# Mega_Shield-criticality.net
KiCad netlist of a schematic drawn in EAGLE
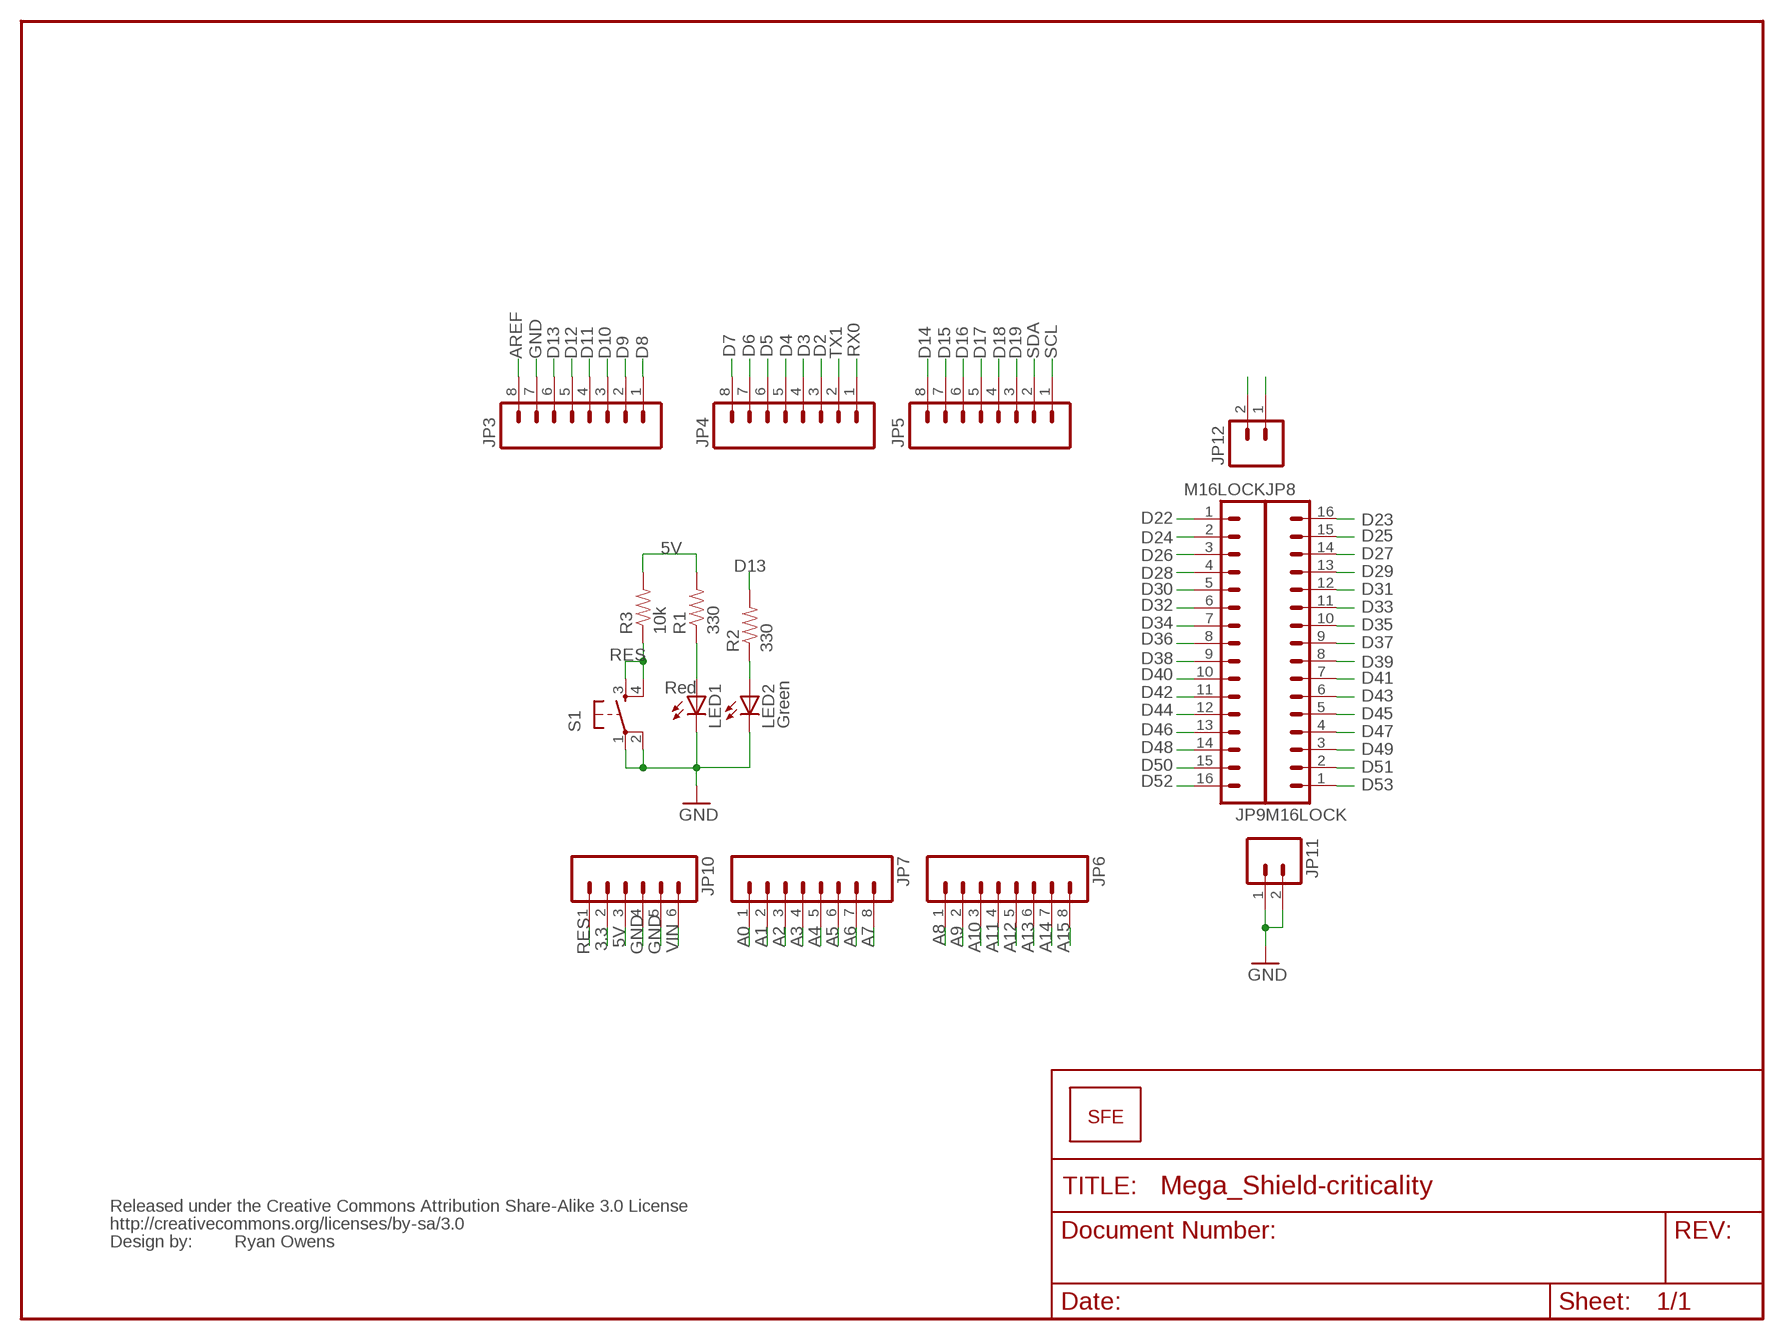
[diagram p0: schematic, sheet 1]

(export (version "E")
  (design (tool "Eeschema 10.0.6"))
  (components
    (comp (ref "JP3")
      (value "M08LOCK")
      (footprint "eagle-import:1X08_LOCK")
      (libsource (lib "eagle-import") (part "M08LOCK"))
    )
    (comp (ref "JP4")
      (value "M08LOCK")
      (footprint "eagle-import:1X08_LOCK")
      (libsource (lib "eagle-import") (part "M08LOCK"))
    )
    (comp (ref "JP5")
      (value "M08LOCK")
      (footprint "eagle-import:1X08_LOCK")
      (libsource (lib "eagle-import") (part "M08LOCK"))
    )
    (comp (ref "JP6")
      (value "M08LOCK")
      (footprint "eagle-import:1X08_LOCK")
      (libsource (lib "eagle-import") (part "M08LOCK"))
    )
    (comp (ref "JP7")
      (value "M08LOCK")
      (footprint "eagle-import:1X08_LOCK")
      (libsource (lib "eagle-import") (part "M08LOCK"))
    )
    (comp (ref "JP8")
      (value "M16LOCK")
      (footprint "eagle-import:1X16_LOCK")
      (libsource (lib "eagle-import") (part "M16LOCK"))
    )
    (comp (ref "JP9")
      (value "M16LOCK")
      (footprint "eagle-import:1X16_LOCK")
      (libsource (lib "eagle-import") (part "M16LOCK"))
    )
    (comp (ref "JP10")
      (value "M06LOCK")
      (footprint "eagle-import:1X06_LOCK")
      (libsource (lib "eagle-import") (part "M06LOCK"))
    )
    (comp (ref "JP11")
      (value "M02LOCK")
      (footprint "eagle-import:1X02_LOCK")
      (libsource (lib "eagle-import") (part "M02LOCK"))
    )
    (comp (ref "JP12")
      (value "M02LOCK")
      (footprint "eagle-import:1X02_LOCK")
      (libsource (lib "eagle-import") (part "M02LOCK"))
    )
    (comp (ref "LED1")
      (value "Red")
      (footprint "eagle-import:LED5MM")
      (libsource (lib "eagle-import") (part "LED5MM"))
    )
    (comp (ref "LED2")
      (value "Green")
      (footprint "eagle-import:LED5MM")
      (libsource (lib "eagle-import") (part "LED5MM"))
    )
    (comp (ref "R1")
      (value "330")
      (footprint "eagle-import:AXIAL-0.3")
      (libsource (lib "eagle-import") (part "RESISTORPTH1"))
    )
    (comp (ref "R2")
      (value "330")
      (footprint "eagle-import:AXIAL-0.3")
      (libsource (lib "eagle-import") (part "RESISTORPTH1"))
    )
    (comp (ref "R3")
      (value "10k")
      (footprint "eagle-import:AXIAL-0.3")
      (libsource (lib "eagle-import") (part "RESISTORPTH1"))
    )
    (comp (ref "S1")
      (value "TAC_SWITCHPTH")
      (footprint "eagle-import:TACTILE-PTH")
      (libsource (lib "eagle-import") (part "TAC_SWITCHPTH"))
    )
    (comp (ref "U$1")
      (value "LOGO-SFENEW")
      (footprint "eagle-import:SFE-NEW-WEBLOGO")
      (libsource (lib "eagle-import") (part "LOGO-SFENEW"))
    )
    (comp (ref "U$2")
      (value "CREATIVE_COMMONS")
      (footprint "eagle-import:CREATIVE_COMMONS")
      (libsource (lib "eagle-import") (part "CREATIVE_COMMONS"))
    )
  )
  (nets
    (net (code "1") (name "/3.3") (class "Default")
      (node (ref "JP10") (pin "2") (pinfunction "2_2") (pintype "passive"))
    )
    (net (code "2") (name "/5V") (class "Default")
      (node (ref "JP10") (pin "3") (pinfunction "3_3") (pintype "passive"))
      (node (ref "R1") (pin "P$2") (pinfunction "2_P$2") (pintype "passive"))
      (node (ref "R3") (pin "P$2") (pinfunction "2_P$2") (pintype "passive"))
    )
    (net (code "3") (name "/5V@1") (class "Default")
      (node (ref "JP12") (pin "1") (pinfunction "1_1") (pintype "passive"))
      (node (ref "JP12") (pin "2") (pinfunction "2_2") (pintype "passive"))
    )
    (net (code "4") (name "/A0") (class "Default")
      (node (ref "JP7") (pin "1") (pinfunction "1_1") (pintype "passive"))
    )
    (net (code "5") (name "/A1") (class "Default")
      (node (ref "JP7") (pin "2") (pinfunction "2_2") (pintype "passive"))
    )
    (net (code "6") (name "/A2") (class "Default")
      (node (ref "JP7") (pin "3") (pinfunction "3_3") (pintype "passive"))
    )
    (net (code "7") (name "/A3") (class "Default")
      (node (ref "JP7") (pin "4") (pinfunction "4_4") (pintype "passive"))
    )
    (net (code "8") (name "/A4") (class "Default")
      (node (ref "JP7") (pin "5") (pinfunction "5_5") (pintype "passive"))
    )
    (net (code "9") (name "/A5") (class "Default")
      (node (ref "JP7") (pin "6") (pinfunction "6_6") (pintype "passive"))
    )
    (net (code "10") (name "/A6") (class "Default")
      (node (ref "JP7") (pin "7") (pinfunction "7_7") (pintype "passive"))
    )
    (net (code "11") (name "/A7") (class "Default")
      (node (ref "JP7") (pin "8") (pinfunction "8_8") (pintype "passive"))
    )
    (net (code "12") (name "/A8") (class "Default")
      (node (ref "JP6") (pin "1") (pinfunction "1_1") (pintype "passive"))
    )
    (net (code "13") (name "/A9") (class "Default")
      (node (ref "JP6") (pin "2") (pinfunction "2_2") (pintype "passive"))
    )
    (net (code "14") (name "/A10") (class "Default")
      (node (ref "JP6") (pin "3") (pinfunction "3_3") (pintype "passive"))
    )
    (net (code "15") (name "/A11") (class "Default")
      (node (ref "JP6") (pin "4") (pinfunction "4_4") (pintype "passive"))
    )
    (net (code "16") (name "/A12") (class "Default")
      (node (ref "JP6") (pin "5") (pinfunction "5_5") (pintype "passive"))
    )
    (net (code "17") (name "/A13") (class "Default")
      (node (ref "JP6") (pin "6") (pinfunction "6_6") (pintype "passive"))
    )
    (net (code "18") (name "/A14") (class "Default")
      (node (ref "JP6") (pin "7") (pinfunction "7_7") (pintype "passive"))
    )
    (net (code "19") (name "/A15") (class "Default")
      (node (ref "JP6") (pin "8") (pinfunction "8_8") (pintype "passive"))
    )
    (net (code "20") (name "/AREF") (class "Default")
      (node (ref "JP3") (pin "8") (pinfunction "8_8") (pintype "passive"))
    )
    (net (code "21") (name "/D2") (class "Default")
      (node (ref "JP4") (pin "3") (pinfunction "3_3") (pintype "passive"))
    )
    (net (code "22") (name "/D3") (class "Default")
      (node (ref "JP4") (pin "4") (pinfunction "4_4") (pintype "passive"))
    )
    (net (code "23") (name "/D4") (class "Default")
      (node (ref "JP4") (pin "5") (pinfunction "5_5") (pintype "passive"))
    )
    (net (code "24") (name "/D5") (class "Default")
      (node (ref "JP4") (pin "6") (pinfunction "6_6") (pintype "passive"))
    )
    (net (code "25") (name "/D6") (class "Default")
      (node (ref "JP4") (pin "7") (pinfunction "7_7") (pintype "passive"))
    )
    (net (code "26") (name "/D7") (class "Default")
      (node (ref "JP4") (pin "8") (pinfunction "8_8") (pintype "passive"))
    )
    (net (code "27") (name "/D8") (class "Default")
      (node (ref "JP3") (pin "1") (pinfunction "1_1") (pintype "passive"))
    )
    (net (code "28") (name "/D9") (class "Default")
      (node (ref "JP3") (pin "2") (pinfunction "2_2") (pintype "passive"))
    )
    (net (code "29") (name "/D10") (class "Default")
      (node (ref "JP3") (pin "3") (pinfunction "3_3") (pintype "passive"))
    )
    (net (code "30") (name "/D11") (class "Default")
      (node (ref "JP3") (pin "4") (pinfunction "4_4") (pintype "passive"))
    )
    (net (code "31") (name "/D12") (class "Default")
      (node (ref "JP3") (pin "5") (pinfunction "5_5") (pintype "passive"))
    )
    (net (code "32") (name "/D13") (class "Default")
      (node (ref "JP3") (pin "6") (pinfunction "6_6") (pintype "passive"))
      (node (ref "R2") (pin "P$2") (pinfunction "2_P$2") (pintype "passive"))
    )
    (net (code "33") (name "/D14") (class "Default")
      (node (ref "JP5") (pin "8") (pinfunction "8_8") (pintype "passive"))
    )
    (net (code "34") (name "/D15") (class "Default")
      (node (ref "JP5") (pin "7") (pinfunction "7_7") (pintype "passive"))
    )
    (net (code "35") (name "/D16") (class "Default")
      (node (ref "JP5") (pin "6") (pinfunction "6_6") (pintype "passive"))
    )
    (net (code "36") (name "/D17") (class "Default")
      (node (ref "JP5") (pin "5") (pinfunction "5_5") (pintype "passive"))
    )
    (net (code "37") (name "/D18") (class "Default")
      (node (ref "JP5") (pin "4") (pinfunction "4_4") (pintype "passive"))
    )
    (net (code "38") (name "/D19") (class "Default")
      (node (ref "JP5") (pin "3") (pinfunction "3_3") (pintype "passive"))
    )
    (net (code "39") (name "/D22") (class "Default")
      (node (ref "JP9") (pin "1") (pinfunction "1_1") (pintype "passive"))
    )
    (net (code "40") (name "/D23") (class "Default")
      (node (ref "JP8") (pin "16") (pinfunction "16_16") (pintype "passive"))
    )
    (net (code "41") (name "/D24") (class "Default")
      (node (ref "JP9") (pin "2") (pinfunction "2_2") (pintype "passive"))
    )
    (net (code "42") (name "/D25") (class "Default")
      (node (ref "JP8") (pin "15") (pinfunction "15_15") (pintype "passive"))
    )
    (net (code "43") (name "/D26") (class "Default")
      (node (ref "JP9") (pin "3") (pinfunction "3_3") (pintype "passive"))
    )
    (net (code "44") (name "/D27") (class "Default")
      (node (ref "JP8") (pin "14") (pinfunction "14_14") (pintype "passive"))
    )
    (net (code "45") (name "/D28") (class "Default")
      (node (ref "JP9") (pin "4") (pinfunction "4_4") (pintype "passive"))
    )
    (net (code "46") (name "/D29") (class "Default")
      (node (ref "JP8") (pin "13") (pinfunction "13_13") (pintype "passive"))
    )
    (net (code "47") (name "/D30") (class "Default")
      (node (ref "JP9") (pin "5") (pinfunction "5_5") (pintype "passive"))
    )
    (net (code "48") (name "/D31") (class "Default")
      (node (ref "JP8") (pin "12") (pinfunction "12_12") (pintype "passive"))
    )
    (net (code "49") (name "/D32") (class "Default")
      (node (ref "JP9") (pin "6") (pinfunction "6_6") (pintype "passive"))
    )
    (net (code "50") (name "/D33") (class "Default")
      (node (ref "JP8") (pin "11") (pinfunction "11_11") (pintype "passive"))
    )
    (net (code "51") (name "/D34") (class "Default")
      (node (ref "JP9") (pin "7") (pinfunction "7_7") (pintype "passive"))
    )
    (net (code "52") (name "/D35") (class "Default")
      (node (ref "JP8") (pin "10") (pinfunction "10_10") (pintype "passive"))
    )
    (net (code "53") (name "/D36") (class "Default")
      (node (ref "JP9") (pin "8") (pinfunction "8_8") (pintype "passive"))
    )
    (net (code "54") (name "/D37") (class "Default")
      (node (ref "JP8") (pin "9") (pinfunction "9_9") (pintype "passive"))
    )
    (net (code "55") (name "/D38") (class "Default")
      (node (ref "JP9") (pin "9") (pinfunction "9_9") (pintype "passive"))
    )
    (net (code "56") (name "/D39") (class "Default")
      (node (ref "JP8") (pin "8") (pinfunction "8_8") (pintype "passive"))
    )
    (net (code "57") (name "/D40") (class "Default")
      (node (ref "JP9") (pin "10") (pinfunction "10_10") (pintype "passive"))
    )
    (net (code "58") (name "/D41") (class "Default")
      (node (ref "JP8") (pin "7") (pinfunction "7_7") (pintype "passive"))
    )
    (net (code "59") (name "/D42") (class "Default")
      (node (ref "JP9") (pin "11") (pinfunction "11_11") (pintype "passive"))
    )
    (net (code "60") (name "/D43") (class "Default")
      (node (ref "JP8") (pin "6") (pinfunction "6_6") (pintype "passive"))
    )
    (net (code "61") (name "/D44") (class "Default")
      (node (ref "JP9") (pin "12") (pinfunction "12_12") (pintype "passive"))
    )
    (net (code "62") (name "/D45") (class "Default")
      (node (ref "JP8") (pin "5") (pinfunction "5_5") (pintype "passive"))
    )
    (net (code "63") (name "/D46") (class "Default")
      (node (ref "JP9") (pin "13") (pinfunction "13_13") (pintype "passive"))
    )
    (net (code "64") (name "/D47") (class "Default")
      (node (ref "JP8") (pin "4") (pinfunction "4_4") (pintype "passive"))
    )
    (net (code "65") (name "/D48") (class "Default")
      (node (ref "JP9") (pin "14") (pinfunction "14_14") (pintype "passive"))
    )
    (net (code "66") (name "/D49") (class "Default")
      (node (ref "JP8") (pin "3") (pinfunction "3_3") (pintype "passive"))
    )
    (net (code "67") (name "/D50") (class "Default")
      (node (ref "JP9") (pin "15") (pinfunction "15_15") (pintype "passive"))
    )
    (net (code "68") (name "/D51") (class "Default")
      (node (ref "JP8") (pin "2") (pinfunction "2_2") (pintype "passive"))
    )
    (net (code "69") (name "/D52") (class "Default")
      (node (ref "JP9") (pin "16") (pinfunction "16_16") (pintype "passive"))
    )
    (net (code "70") (name "/D53") (class "Default")
      (node (ref "JP8") (pin "1") (pinfunction "1_1") (pintype "passive"))
    )
    (net (code "71") (name "/RES") (class "Default")
      (node (ref "JP10") (pin "1") (pinfunction "1_1") (pintype "passive"))
      (node (ref "R3") (pin "P$1") (pinfunction "1_P$1") (pintype "passive"))
      (node (ref "S1") (pin "3") (pinfunction "3_3") (pintype "passive"))
      (node (ref "S1") (pin "4") (pinfunction "4_4") (pintype "passive"))
    )
    (net (code "72") (name "/RX0") (class "Default")
      (node (ref "JP4") (pin "1") (pinfunction "1_1") (pintype "passive"))
    )
    (net (code "73") (name "/SCL") (class "Default")
      (node (ref "JP5") (pin "1") (pinfunction "1_1") (pintype "passive"))
    )
    (net (code "74") (name "/SDA") (class "Default")
      (node (ref "JP5") (pin "2") (pinfunction "2_2") (pintype "passive"))
    )
    (net (code "75") (name "/TX1") (class "Default")
      (node (ref "JP4") (pin "2") (pinfunction "2_2") (pintype "passive"))
    )
    (net (code "76") (name "/VIN") (class "Default")
      (node (ref "JP10") (pin "6") (pinfunction "6_6") (pintype "passive"))
    )
    (net (code "77") (name "GND") (class "Default")
      (node (ref "JP10") (pin "4") (pinfunction "4_4") (pintype "passive"))
      (node (ref "JP10") (pin "5") (pinfunction "5_5") (pintype "passive"))
      (node (ref "JP11") (pin "1") (pinfunction "1_1") (pintype "passive"))
      (node (ref "JP11") (pin "2") (pinfunction "2_2") (pintype "passive"))
      (node (ref "JP3") (pin "7") (pinfunction "7_7") (pintype "passive"))
      (node (ref "LED1") (pin "K") (pinfunction "C_K") (pintype "passive"))
      (node (ref "LED2") (pin "K") (pinfunction "C_K") (pintype "passive"))
      (node (ref "S1") (pin "1") (pinfunction "1_1") (pintype "passive"))
      (node (ref "S1") (pin "2") (pinfunction "2_2") (pintype "passive"))
    )
    (net (code "78") (name "Net-(R1-1)") (class "Default")
      (node (ref "LED1") (pin "A") (pinfunction "A_A") (pintype "passive"))
      (node (ref "R1") (pin "P$1") (pinfunction "1_P$1") (pintype "passive"))
    )
    (net (code "79") (name "Net-(R2-1)") (class "Default")
      (node (ref "LED2") (pin "A") (pinfunction "A_A") (pintype "passive"))
      (node (ref "R2") (pin "P$1") (pinfunction "1_P$1") (pintype "passive"))
    )
  )
)
